# Mother_Board_NRF24L01.net
KiCad netlist of a schematic drawn in Altium Designer
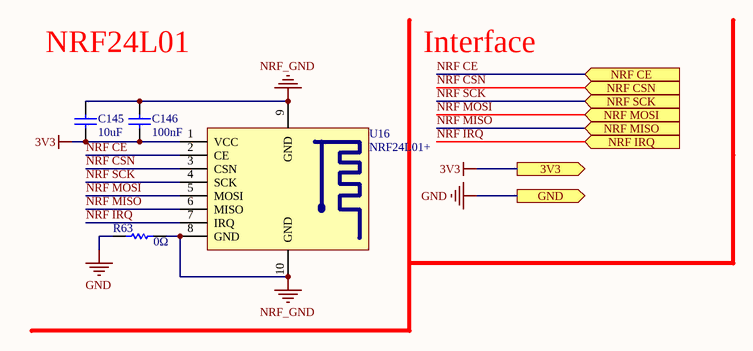
[diagram p0: Mother Board NRF24L01.SchDoc]

(export (version "E")
  (design (tool "Eeschema 10.0.6"))
  (components
    (comp (ref "C145") (value "10uF") (footprint "C0805") (libsource (lib "Cap") (part "Cap")))
    (comp (ref "C146") (value "100nF") (footprint "C0603") (libsource (lib "Cap") (part "Cap")))
    (comp (ref "R63") (value "0Ω") (footprint "R0603") (libsource (lib "Res") (part "RES")))
    (comp (ref "U16")
      (value "NRF24L01+")
      (footprint "NRF24L01+")
      (libsource (lib "All lib") (part "NRF24L01+"))
    )
  )
  (nets
    (net (code "1") (name "/NRF CE") (class "Default")
      (node (ref "U16") (pin "2") (pinfunction "CE_2") (pintype "passive"))
    )
    (net (code "2") (name "/NRF CSN") (class "Default")
      (node (ref "U16") (pin "3") (pinfunction "CSN_3") (pintype "passive"))
    )
    (net (code "3") (name "/NRF IRQ") (class "Default")
      (node (ref "U16") (pin "7") (pinfunction "IRQ_7") (pintype "passive"))
    )
    (net (code "4") (name "/NRF MISO") (class "Default")
      (node (ref "U16") (pin "6") (pinfunction "MISO_6") (pintype "passive"))
    )
    (net (code "5") (name "/NRF MOSI") (class "Default")
      (node (ref "U16") (pin "5") (pinfunction "MOSI_5") (pintype "passive"))
    )
    (net (code "6") (name "/NRF SCK") (class "Default")
      (node (ref "U16") (pin "4") (pinfunction "SCK_4") (pintype "passive"))
    )
    (net (code "7") (name "3V3") (class "Default")
      (node (ref "C145") (pin "1") (pinfunction "1_1") (pintype "passive"))
      (node (ref "C146") (pin "1") (pinfunction "1_1") (pintype "passive"))
      (node (ref "U16") (pin "1") (pinfunction "VCC_1") (pintype "passive"))
    )
    (net (code "8") (name "GND") (class "Default")
      (node (ref "R63") (pin "2") (pinfunction "2_2") (pintype "passive"))
    )
    (net (code "9") (name "NRF_GND") (class "Default")
      (node (ref "C145") (pin "2") (pinfunction "2_2") (pintype "passive"))
      (node (ref "C146") (pin "2") (pinfunction "2_2") (pintype "passive"))
      (node (ref "R63") (pin "1") (pinfunction "1_1") (pintype "passive"))
      (node (ref "U16") (pin "10") (pinfunction "GND_10") (pintype "passive"))
      (node (ref "U16") (pin "8") (pinfunction "GND_8") (pintype "passive"))
      (node (ref "U16") (pin "9") (pinfunction "GND_9") (pintype "passive"))
    )
  )
)
